# FPGA.net
KiCad netlist of a schematic drawn in Altium Designer
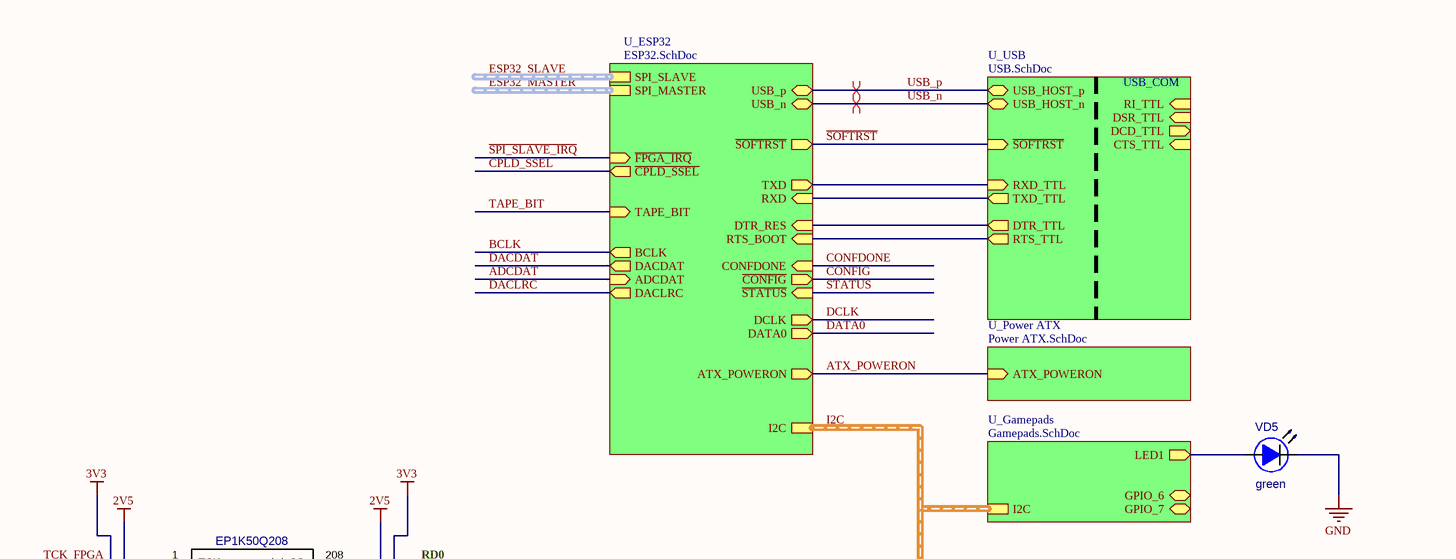
[diagram p0: FPGA.SchDoc, top]
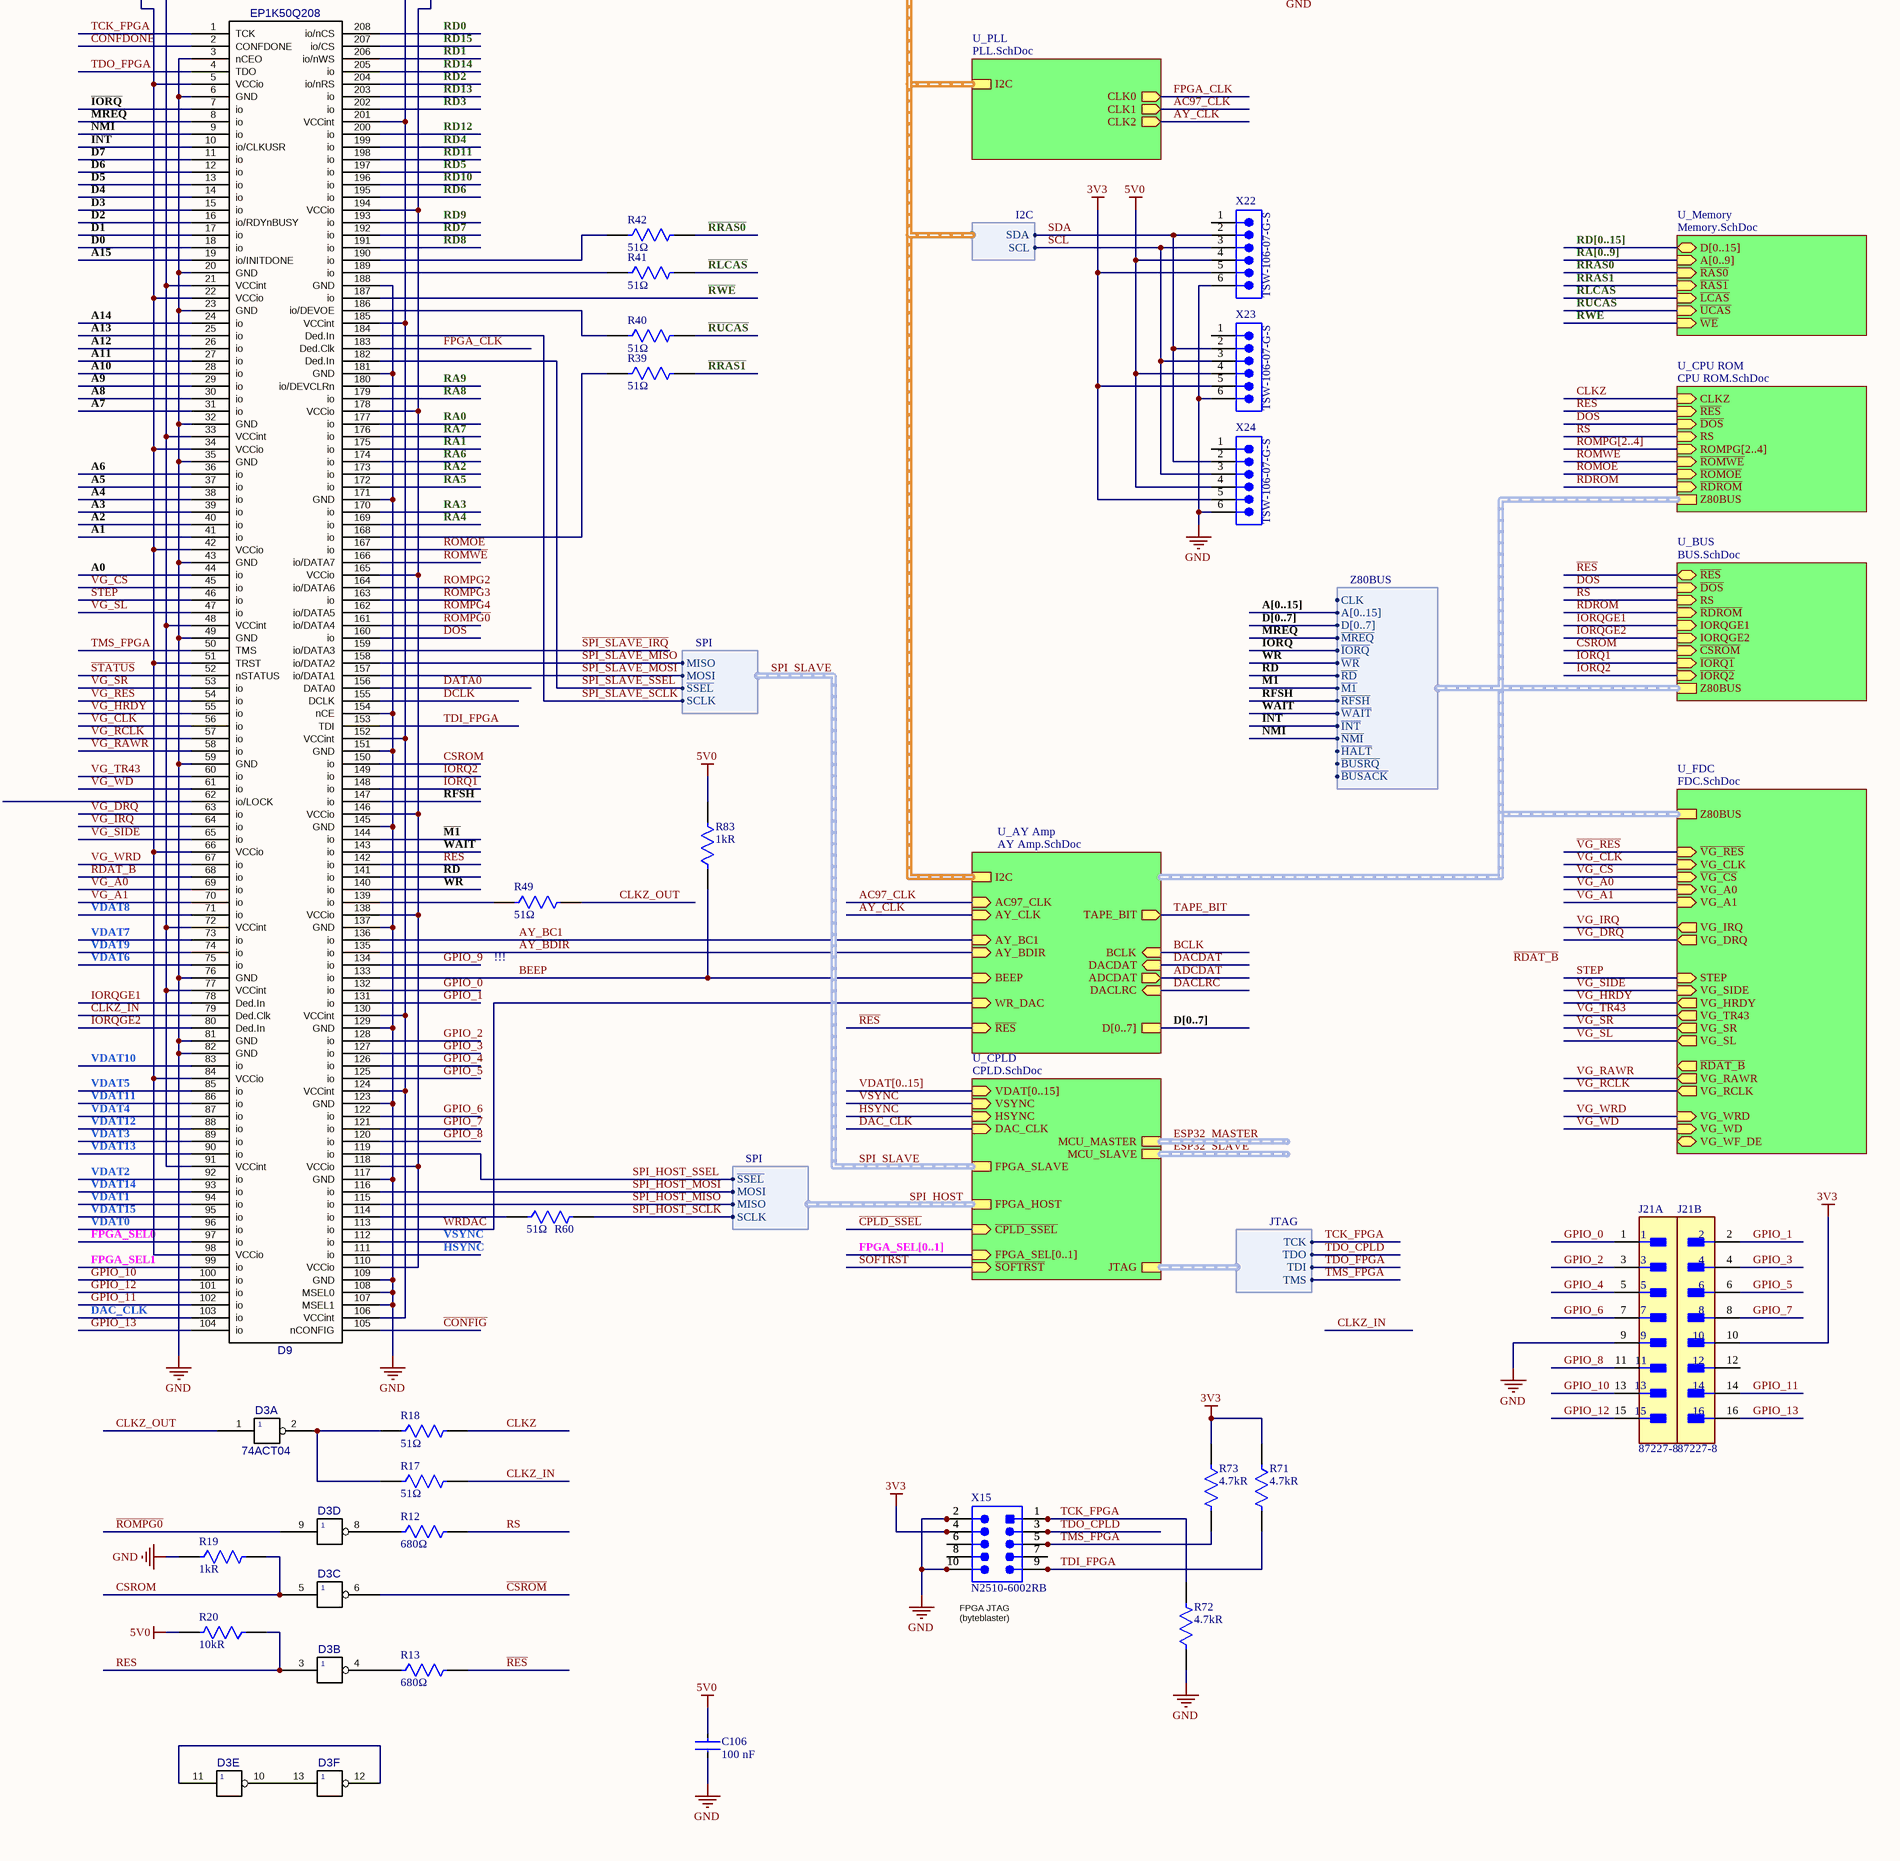
[diagram p1: FPGA.SchDoc, bottom]

(export (version "E")
  (design (tool "Eeschema 10.0.6"))
  (components
    (comp (ref "C106")
      (value "CC0805KRX7R9BB104")
      (footprint "FP-CC0805-0_85-IPC_A")
      (description "CAP CER 0.1UF 50V X7R 0805")
      (fields (field (name "CAPACITANCE") "100 nF") (field (name "MANUFACTURER") "Yageo"))
      (libsource (lib "SchLib") (part "CMP-2100-03606-3"))
    )
    (comp (ref "D3")
      (value "74ACT04")
      (footprint "SO14")
      (description "04")
      (libsource (lib "SchLib") (part "04"))
    )
    (comp (ref "D9")
      (value "EP1K50Q208")
      (footprint "PQFP208X5")
      (libsource (lib "SchLib") (part "EP1K50Q208"))
    )
    (comp (ref "J21")
      (value "87227-8")
      (footprint "FP-87227-8-MFG")
      (description "CONN HEADER VERT 16POS 2.54MM")
      (fields (field (name "MANUFACTURER") "TE Connectivity"))
      (libsource (lib "") (part "CMP-03369-000064-1_1"))
    )
    (comp (ref "R12")
      (value "680Ω")
      (footprint "FP-RT0805-IPC_A")
      (description "RES SMD 680 OHM 1% 1/8W 0805")
      (fields
        (field (name "MANUFACTURER") "Yageo")
        (field (name "MANUFACTURER PART NUMBER") "RT0805FRE07680RL")
      )
      (libsource (lib "SchLib") (part "CMP-03412-000082-1"))
    )
    (comp (ref "R13")
      (value "680Ω")
      (footprint "FP-RT0805-IPC_A")
      (description "RES SMD 680 OHM 1% 1/8W 0805")
      (fields
        (field (name "MANUFACTURER") "Yageo")
        (field (name "MANUFACTURER PART NUMBER") "RT0805FRE07680RL")
      )
      (libsource (lib "SchLib") (part "CMP-03412-000082-1"))
    )
    (comp (ref "R17")
      (value "RR1220Q-510-D")
      (footprint "FP-RR1220-IPC_A")
      (description "51Ω ±0.5% 0.1W 1/10W Chip Resistor 0805 (2012 Metric) Thin Film")
      (fields (field (name "RESISTANCE") "51Ω") (field (name "MANUFACTURER") "Susumu"))
      (libsource (lib "SchLib") (part "CMP-2001-03561-2"))
    )
    (comp (ref "R18")
      (value "RR1220Q-510-D")
      (footprint "FP-RR1220-IPC_A")
      (description "51Ω ±0.5% 0.1W 1/10W Chip Resistor 0805 (2012 Metric) Thin Film")
      (fields (field (name "RESISTANCE") "51Ω") (field (name "MANUFACTURER") "Susumu"))
      (libsource (lib "SchLib") (part "CMP-2001-03561-2"))
    )
    (comp (ref "R19")
      (value "CRCW08051K00FKEAHP")
      (footprint "FP-CRCW0805-HPe3-IPC_A")
      (description "RES Thick Film, 1kΩ, 1%, 0.5W, 100ppm/°C, 0805")
      (fields (field (name "RESISTANCE") "1kR") (field (name "MANUFACTURER") "Vishay Dale"))
      (libsource (lib "SchLib") (part "CMP-02407-004529-1"))
    )
    (comp (ref "R20")
      (value "CR0805-JW-103ELF")
      (footprint "FP-CR0805-IPC_A")
      (description "Thick Film Chip Resistors 0805 10kΩ 0.125W 5% 200ppm/°C")
      (fields (field (name "RESISTANCE") "10kR") (field (name "MANUFACTURER") "Bourns"))
      (libsource (lib "SchLib") (part "CMP-07231-003873-1"))
    )
    (comp (ref "R39")
      (value "RR1220Q-510-D")
      (footprint "FP-RR1220-IPC_A")
      (description "51Ω ±0.5% 0.1W 1/10W Chip Resistor 0805 (2012 Metric) Thin Film")
      (fields (field (name "RESISTANCE") "51Ω") (field (name "MANUFACTURER") "Susumu"))
      (libsource (lib "SchLib") (part "CMP-2001-03561-2"))
    )
    (comp (ref "R40")
      (value "RR1220Q-510-D")
      (footprint "FP-RR1220-IPC_A")
      (description "51Ω ±0.5% 0.1W 1/10W Chip Resistor 0805 (2012 Metric) Thin Film")
      (fields (field (name "RESISTANCE") "51Ω") (field (name "MANUFACTURER") "Susumu"))
      (libsource (lib "SchLib") (part "CMP-2001-03561-2"))
    )
    (comp (ref "R41")
      (value "RR1220Q-510-D")
      (footprint "FP-RR1220-IPC_A")
      (description "51Ω ±0.5% 0.1W 1/10W Chip Resistor 0805 (2012 Metric) Thin Film")
      (fields (field (name "RESISTANCE") "51Ω") (field (name "MANUFACTURER") "Susumu"))
      (libsource (lib "SchLib") (part "CMP-2001-03561-2"))
    )
    (comp (ref "R42")
      (value "RR1220Q-510-D")
      (footprint "FP-RR1220-IPC_A")
      (description "51Ω ±0.5% 0.1W 1/10W Chip Resistor 0805 (2012 Metric) Thin Film")
      (fields (field (name "RESISTANCE") "51Ω") (field (name "MANUFACTURER") "Susumu"))
      (libsource (lib "SchLib") (part "CMP-2001-03561-2"))
    )
    (comp (ref "R49")
      (value "RR1220Q-510-D")
      (footprint "FP-RR1220-IPC_A")
      (description "51Ω ±0.5% 0.1W 1/10W Chip Resistor 0805 (2012 Metric) Thin Film")
      (fields (field (name "RESISTANCE") "51Ω") (field (name "MANUFACTURER") "Susumu"))
      (libsource (lib "SchLib") (part "CMP-2001-03561-2"))
    )
    (comp (ref "R60")
      (value "RR1220Q-510-D")
      (footprint "FP-RR1220-IPC_A")
      (description "51Ω ±0.5% 0.1W 1/10W Chip Resistor 0805 (2012 Metric) Thin Film")
      (fields (field (name "RESISTANCE") "51Ω") (field (name "MANUFACTURER") "Susumu"))
      (libsource (lib "SchLib") (part "CMP-2001-03561-2"))
    )
    (comp (ref "R71")
      (value "CR0805-JW-472ELF")
      (footprint "FP-CR0805-IPC_A")
      (description "Thick Film Chip Resistors 0805 4.7kΩ 0.125W 5% 200ppm/°C")
      (fields (field (name "RESISTANCE") "4.7kR") (field (name "MANUFACTURER") "Bourns"))
      (libsource (lib "SchLib") (part "CMP-07231-004713-1"))
    )
    (comp (ref "R72")
      (value "CR0805-JW-472ELF")
      (footprint "FP-CR0805-IPC_A")
      (description "Thick Film Chip Resistors 0805 4.7kΩ 0.125W 5% 200ppm/°C")
      (fields (field (name "RESISTANCE") "4.7kR") (field (name "MANUFACTURER") "Bourns"))
      (libsource (lib "SchLib") (part "CMP-07231-004713-1"))
    )
    (comp (ref "R73")
      (value "CR0805-JW-472ELF")
      (footprint "FP-CR0805-IPC_A")
      (description "Thick Film Chip Resistors 0805 4.7kΩ 0.125W 5% 200ppm/°C")
      (fields (field (name "RESISTANCE") "4.7kR") (field (name "MANUFACTURER") "Bourns"))
      (libsource (lib "SchLib") (part "CMP-07231-004713-1"))
    )
    (comp (ref "R83")
      (value "CRCW08051K00FKEAHP")
      (footprint "FP-CRCW0805-HPe3-IPC_A")
      (description "RES Thick Film, 1kΩ, 1%, 0.5W, 100ppm/°C, 0805")
      (fields (field (name "RESISTANCE") "1kR") (field (name "MANUFACTURER") "Vishay Dale"))
      (libsource (lib "SchLib") (part "CMP-02407-004529-1"))
    )
    (comp (ref "VD5")
      (value "green")
      (footprint "LED100_LED(Primary)")
      (description "Light Emitting Diode")
      (fields (field (name "Comment") "LED"))
      (libsource (lib "SchLib") (part "LED"))
    )
    (comp (ref "X15")
      (value "N2510-6002RB")
      (footprint "3M-N2510-6002-10_V")
      (fields (field (name "PARTNUMBER") "N2510") (field (name "MANUFACTURER") "3M"))
      (libsource (lib "SchLib") (part "CMP-2000-06794-1"))
    )
    (comp (ref "X22")
      (value "TSW-106-07-G-S")
      (footprint "SMTC-TSW-106-07-X-S")
      (description "0.025\" SQ Post Header, Through-hole, Vertical, -55 to 125 degC, 2.54 mm Pitch, 6-Pin, Male, RoHS")
      (fields (field (name "MANUFACTURER") "Samtec"))
      (libsource (lib "SchLib") (part "CMP-1024-00383-1"))
    )
    (comp (ref "X23")
      (value "TSW-106-07-G-S")
      (footprint "SMTC-TSW-106-07-X-S")
      (description "0.025\" SQ Post Header, Through-hole, Vertical, -55 to 125 degC, 2.54 mm Pitch, 6-Pin, Male, RoHS")
      (fields (field (name "MANUFACTURER") "Samtec"))
      (libsource (lib "SchLib") (part "CMP-1024-00383-1"))
    )
    (comp (ref "X24")
      (value "TSW-106-07-G-S")
      (footprint "SMTC-TSW-106-07-X-S")
      (description "0.025\" SQ Post Header, Through-hole, Vertical, -55 to 125 degC, 2.54 mm Pitch, 6-Pin, Male, RoHS")
      (fields (field (name "MANUFACTURER") "Samtec"))
      (libsource (lib "SchLib") (part "CMP-1024-00383-1"))
    )
  )
  (nets
    (net (code "7") (name "+5v") (class "Default")
      (node (ref "D3") (pin "14") (pinfunction "+5v_14") (pintype "power_in"))
    )
    (net (code "8") (name "/A0") (class "Default")
      (node (ref "D9") (pin "44") (pinfunction "io_44") (pintype "passive"))
    )
    (net (code "9") (name "/A1") (class "Default")
      (node (ref "D9") (pin "41") (pinfunction "io_41") (pintype "passive"))
    )
    (net (code "10") (name "/A2") (class "Default")
      (node (ref "D9") (pin "40") (pinfunction "io_40") (pintype "passive"))
    )
    (net (code "11") (name "/A3") (class "Default")
      (node (ref "D9") (pin "39") (pinfunction "io_39") (pintype "passive"))
    )
    (net (code "12") (name "/A4") (class "Default")
      (node (ref "D9") (pin "38") (pinfunction "io_38") (pintype "passive"))
    )
    (net (code "13") (name "/A5") (class "Default")
      (node (ref "D9") (pin "37") (pinfunction "io_37") (pintype "passive"))
    )
    (net (code "14") (name "/A6") (class "Default")
      (node (ref "D9") (pin "36") (pinfunction "io_36") (pintype "passive"))
    )
    (net (code "15") (name "/A7") (class "Default")
      (node (ref "D9") (pin "31") (pinfunction "io_31") (pintype "passive"))
    )
    (net (code "16") (name "/A8") (class "Default")
      (node (ref "D9") (pin "30") (pinfunction "io_30") (pintype "passive"))
    )
    (net (code "17") (name "/A9") (class "Default")
      (node (ref "D9") (pin "29") (pinfunction "io_29") (pintype "passive"))
    )
    (net (code "18") (name "/A10") (class "Default")
      (node (ref "D9") (pin "28") (pinfunction "io_28") (pintype "passive"))
    )
    (net (code "19") (name "/A11") (class "Default")
      (node (ref "D9") (pin "27") (pinfunction "io_27") (pintype "passive"))
    )
    (net (code "20") (name "/A12") (class "Default")
      (node (ref "D9") (pin "26") (pinfunction "io_26") (pintype "passive"))
    )
    (net (code "21") (name "/A13") (class "Default")
      (node (ref "D9") (pin "25") (pinfunction "io_25") (pintype "passive"))
    )
    (net (code "22") (name "/A14") (class "Default")
      (node (ref "D9") (pin "24") (pinfunction "io_24") (pintype "passive"))
    )
    (net (code "23") (name "/A15") (class "Default")
      (node (ref "D9") (pin "19") (pinfunction "io/INITDONE_19") (pintype "passive"))
    )
    (net (code "27") (name "/AY_BC1") (class "Default")
      (node (ref "D9") (pin "136") (pinfunction "io_136") (pintype "passive"))
    )
    (net (code "28") (name "/AY_BDIR") (class "Default")
      (node (ref "D9") (pin "135") (pinfunction "io_135") (pintype "passive"))
    )
    (net (code "32") (name "/BEEP") (class "Default")
      (node (ref "D9") (pin "133") (pinfunction "io_133") (pintype "passive"))
      (node (ref "R83") (pin "1") (pinfunction "1_1") (pintype "passive"))
    )
    (net (code "33") (name "/CLKZ") (class "Default")
      (node (ref "R18") (pin "2") (pinfunction "2_2") (pintype "passive"))
    )
    (net (code "34") (name "/CLKZ_IN") (class "Default")
      (node (ref "D9") (pin "79") (pinfunction "Ded.Clk_79") (pintype "passive"))
      (node (ref "R17") (pin "2") (pinfunction "2_2") (pintype "passive"))
    )
    (net (code "35") (name "/CLKZ_OUT") (class "Default")
      (node (ref "D3") (pin "1") (pintype "passive"))
      (node (ref "R49") (pin "2") (pinfunction "2_2") (pintype "passive"))
    )
    (net (code "36") (name "/CONFDONE") (class "Default")
      (node (ref "D9") (pin "2") (pinfunction "CONFDONE_2") (pintype "passive"))
    )
    (net (code "37") (name "/CSROM") (class "Default")
      (node (ref "D3") (pin "5") (pintype "passive"))
      (node (ref "D9") (pin "150") (pinfunction "io_150") (pintype "passive"))
      (node (ref "R19") (pin "2") (pinfunction "2_2") (pintype "passive"))
    )
    (net (code "39") (name "/D0") (class "Default")
      (node (ref "D9") (pin "18") (pinfunction "io_18") (pintype "passive"))
    )
    (net (code "40") (name "/D1") (class "Default")
      (node (ref "D9") (pin "17") (pinfunction "io_17") (pintype "passive"))
    )
    (net (code "41") (name "/D2") (class "Default")
      (node (ref "D9") (pin "16") (pinfunction "io/RDYnBUSY_16") (pintype "passive"))
    )
    (net (code "42") (name "/D3") (class "Default")
      (node (ref "D9") (pin "15") (pinfunction "io_15") (pintype "passive"))
    )
    (net (code "43") (name "/D4") (class "Default")
      (node (ref "D9") (pin "14") (pinfunction "io_14") (pintype "passive"))
    )
    (net (code "44") (name "/D5") (class "Default")
      (node (ref "D9") (pin "13") (pinfunction "io_13") (pintype "passive"))
    )
    (net (code "45") (name "/D6") (class "Default")
      (node (ref "D9") (pin "12") (pinfunction "io_12") (pintype "passive"))
    )
    (net (code "46") (name "/D7") (class "Default")
      (node (ref "D9") (pin "11") (pinfunction "io_11") (pintype "passive"))
    )
    (net (code "49") (name "/DAC_CLK") (class "Default")
      (node (ref "D9") (pin "103") (pinfunction "io_103") (pintype "passive"))
    )
    (net (code "50") (name "/DATA0") (class "Default")
      (node (ref "D9") (pin "156") (pinfunction "DATA0_156") (pintype "passive"))
    )
    (net (code "52") (name "/DCLK") (class "Default")
      (node (ref "D9") (pin "155") (pinfunction "DCLK_155") (pintype "passive"))
    )
    (net (code "56") (name "/FPGA_CLK") (class "Default")
      (node (ref "D9") (pin "183") (pinfunction "Ded.Clk_183") (pintype "passive"))
    )
    (net (code "57") (name "/FPGA_SEL0") (class "Default")
      (node (ref "D9") (pin "97") (pinfunction "io_97") (pintype "passive"))
    )
    (net (code "58") (name "/FPGA_SEL1") (class "Default")
      (node (ref "D9") (pin "99") (pinfunction "io_99") (pintype "passive"))
    )
    (net (code "60") (name "/GPIO_0") (class "Default")
      (node (ref "D9") (pin "132") (pinfunction "io_132") (pintype "passive"))
      (node (ref "J21") (pin "1") (pinfunction "1_1") (pintype "passive"))
    )
    (net (code "61") (name "/GPIO_1") (class "Default")
      (node (ref "D9") (pin "131") (pinfunction "io_131") (pintype "passive"))
      (node (ref "J21") (pin "2") (pinfunction "2_2") (pintype "passive"))
    )
    (net (code "62") (name "/GPIO_2") (class "Default")
      (node (ref "D9") (pin "128") (pinfunction "io_128") (pintype "passive"))
      (node (ref "J21") (pin "3") (pinfunction "3_3") (pintype "passive"))
    )
    (net (code "63") (name "/GPIO_3") (class "Default")
      (node (ref "D9") (pin "127") (pinfunction "io_127") (pintype "passive"))
      (node (ref "J21") (pin "4") (pinfunction "4_4") (pintype "passive"))
    )
    (net (code "64") (name "/GPIO_4") (class "Default")
      (node (ref "D9") (pin "126") (pinfunction "io_126") (pintype "passive"))
      (node (ref "J21") (pin "5") (pinfunction "5_5") (pintype "passive"))
    )
    (net (code "65") (name "/GPIO_5") (class "Default")
      (node (ref "D9") (pin "125") (pinfunction "io_125") (pintype "passive"))
      (node (ref "J21") (pin "6") (pinfunction "6_6") (pintype "passive"))
    )
    (net (code "66") (name "/GPIO_6") (class "Default")
      (node (ref "D9") (pin "122") (pinfunction "io_122") (pintype "passive"))
      (node (ref "J21") (pin "7") (pinfunction "7_7") (pintype "passive"))
    )
    (net (code "68") (name "/GPIO_7") (class "Default")
      (node (ref "D9") (pin "121") (pinfunction "io_121") (pintype "passive"))
      (node (ref "J21") (pin "8") (pinfunction "8_8") (pintype "passive"))
    )
    (net (code "70") (name "/GPIO_8") (class "Default")
      (node (ref "D9") (pin "120") (pinfunction "io_120") (pintype "passive"))
      (node (ref "J21") (pin "11") (pinfunction "11_11") (pintype "passive"))
    )
    (net (code "71") (name "/GPIO_9") (class "Default")
      (node (ref "D9") (pin "134") (pinfunction "io_134") (pintype "passive"))
    )
    (net (code "72") (name "/GPIO_10") (class "Default")
      (node (ref "D9") (pin "100") (pinfunction "io_100") (pintype "passive"))
      (node (ref "J21") (pin "13") (pinfunction "13_13") (pintype "passive"))
    )
    (net (code "73") (name "/GPIO_11") (class "Default")
      (node (ref "D9") (pin "102") (pinfunction "io_102") (pintype "passive"))
      (node (ref "J21") (pin "14") (pinfunction "14_14") (pintype "passive"))
    )
    (net (code "74") (name "/GPIO_12") (class "Default")
      (node (ref "D9") (pin "101") (pinfunction "io_101") (pintype "passive"))
      (node (ref "J21") (pin "15") (pinfunction "15_15") (pintype "passive"))
    )
    (net (code "75") (name "/GPIO_13") (class "Default")
      (node (ref "D9") (pin "104") (pinfunction "io_104") (pintype "passive"))
      (node (ref "J21") (pin "16") (pinfunction "16_16") (pintype "passive"))
    )
    (net (code "76") (name "/HSYNC") (class "Default")
      (node (ref "D9") (pin "111") (pinfunction "io_111") (pintype "passive"))
    )
    (net (code "78") (name "/IORQGE1") (class "Default")
      (node (ref "D9") (pin "78") (pinfunction "Ded.In_78") (pintype "passive"))
    )
    (net (code "79") (name "/IORQGE2") (class "Default")
      (node (ref "D9") (pin "80") (pinfunction "Ded.In_80") (pintype "passive"))
    )
    (net (code "80") (name "/LED1") (class "Default")
      (node (ref "VD5") (pin "A") (pinfunction "A_A") (pintype "passive"))
    )
    (net (code "81") (name "/RA0") (class "Default")
      (node (ref "D9") (pin "177") (pinfunction "io_177") (pintype "passive"))
    )
    (net (code "82") (name "/RA1") (class "Default")
      (node (ref "D9") (pin "175") (pinfunction "io_175") (pintype "passive"))
    )
    (net (code "83") (name "/RA2") (class "Default")
      (node (ref "D9") (pin "173") (pinfunction "io_173") (pintype "passive"))
    )
    (net (code "84") (name "/RA3") (class "Default")
      (node (ref "D9") (pin "170") (pinfunction "io_170") (pintype "passive"))
    )
    (net (code "85") (name "/RA4") (class "Default")
      (node (ref "D9") (pin "169") (pinfunction "io_169") (pintype "passive"))
    )
    (net (code "86") (name "/RA5") (class "Default")
      (node (ref "D9") (pin "172") (pinfunction "io_172") (pintype "passive"))
    )
    (net (code "87") (name "/RA6") (class "Default")
      (node (ref "D9") (pin "174") (pinfunction "io_174") (pintype "passive"))
    )
    (net (code "88") (name "/RA7") (class "Default")
      (node (ref "D9") (pin "176") (pinfunction "io_176") (pintype "passive"))
    )
    (net (code "89") (name "/RA8") (class "Default")
      (node (ref "D9") (pin "179") (pinfunction "io_179") (pintype "passive"))
    )
    (net (code "90") (name "/RA9") (class "Default")
      (node (ref "D9") (pin "180") (pinfunction "io/DEVCLRn_180") (pintype "passive"))
    )
    (net (code "92") (name "/RD0") (class "Default")
      (node (ref "D9") (pin "208") (pinfunction "io/nCS_208") (pintype "passive"))
    )
    (net (code "93") (name "/RD1") (class "Default")
      (node (ref "D9") (pin "206") (pinfunction "io/nWS_206") (pintype "passive"))
    )
    (net (code "94") (name "/RD2") (class "Default")
      (node (ref "D9") (pin "204") (pinfunction "io/nRS_204") (pintype "passive"))
    )
    (net (code "95") (name "/RD3") (class "Default")
      (node (ref "D9") (pin "202") (pinfunction "io_202") (pintype "passive"))
    )
    (net (code "96") (name "/RD4") (class "Default")
      (node (ref "D9") (pin "199") (pinfunction "io_199") (pintype "passive"))
    )
    (net (code "97") (name "/RD5") (class "Default")
      (node (ref "D9") (pin "197") (pinfunction "io_197") (pintype "passive"))
    )
    (net (code "98") (name "/RD6") (class "Default")
      (node (ref "D9") (pin "195") (pinfunction "io_195") (pintype "passive"))
    )
    (net (code "99") (name "/RD7") (class "Default")
      (node (ref "D9") (pin "192") (pinfunction "io_192") (pintype "passive"))
    )
    (net (code "100") (name "/RD8") (class "Default")
      (node (ref "D9") (pin "191") (pinfunction "io_191") (pintype "passive"))
    )
    (net (code "101") (name "/RD9") (class "Default")
      (node (ref "D9") (pin "193") (pinfunction "io_193") (pintype "passive"))
    )
    (net (code "102") (name "/RD10") (class "Default")
      (node (ref "D9") (pin "196") (pinfunction "io_196") (pintype "passive"))
    )
    (net (code "103") (name "/RD11") (class "Default")
      (node (ref "D9") (pin "198") (pinfunction "io_198") (pintype "passive"))
    )
    (net (code "104") (name "/RD12") (class "Default")
      (node (ref "D9") (pin "200") (pinfunction "io_200") (pintype "passive"))
    )
    (net (code "105") (name "/RD13") (class "Default")
      (node (ref "D9") (pin "203") (pinfunction "io_203") (pintype "passive"))
    )
    (net (code "106") (name "/RD14") (class "Default")
      (node (ref "D9") (pin "205") (pinfunction "io_205") (pintype "passive"))
    )
    (net (code "107") (name "/RD15") (class "Default")
      (node (ref "D9") (pin "207") (pinfunction "io/CS_207") (pintype "passive"))
    )
    (net (code "109") (name "/RES") (class "Default")
      (node (ref "D3") (pin "3") (pintype "passive"))
      (node (ref "D9") (pin "142") (pinfunction "io_142") (pintype "passive"))
      (node (ref "R20") (pin "1") (pinfunction "1_1") (pintype "passive"))
    )
    (net (code "111") (name "/ROMPG2") (class "Default")
      (node (ref "D9") (pin "164") (pinfunction "io/DATA6_164") (pintype "passive"))
    )
    (net (code "112") (name "/ROMPG3") (class "Default")
      (node (ref "D9") (pin "163") (pinfunction "io_163") (pintype "passive"))
    )
    (net (code "113") (name "/ROMPG4") (class "Default")
      (node (ref "D9") (pin "162") (pinfunction "io/DATA5_162") (pintype "passive"))
    )
    (net (code "115") (name "/RS") (class "Default")
      (node (ref "R12") (pin "2") (pinfunction "2_2") (pintype "passive"))
    )
    (net (code "117") (name "/SCL") (class "Default")
      (node (ref "X22") (pin "3") (pinfunction "3_3") (pintype "passive"))
      (node (ref "X23") (pin "3") (pinfunction "3_3") (pintype "passive"))
      (node (ref "X24") (pin "3") (pinfunction "3_3") (pintype "passive"))
    )
    (net (code "118") (name "/SDA") (class "Default")
      (node (ref "X22") (pin "2") (pinfunction "2_2") (pintype "passive"))
      (node (ref "X23") (pin "2") (pinfunction "2_2") (pintype "passive"))
      (node (ref "X24") (pin "2") (pinfunction "2_2") (pintype "passive"))
    )
    (net (code "119") (name "/SPI_HOST_MISO") (class "Default")
      (node (ref "D9") (pin "115") (pinfunction "io_115") (pintype "passive"))
    )
    (net (code "120") (name "/SPI_HOST_MOSI") (class "Default")
      (node (ref "D9") (pin "116") (pinfunction "io_116") (pintype "passive"))
    )
    (net (code "121") (name "/SPI_HOST_SCLK") (class "Default")
      (node (ref "R60") (pin "2") (pinfunction "2_2") (pintype "passive"))
    )
    (net (code "122") (name "/SPI_HOST_SSEL") (class "Default")
      (node (ref "D9") (pin "119") (pinfunction "io_119") (pintype "passive"))
    )
    (net (code "124") (name "/SPI_SLAVE_MISO") (class "Default")
      (node (ref "D9") (pin "158") (pinfunction "io/DATA2_158") (pintype "passive"))
    )
    (net (code "125") (name "/SPI_SLAVE_MOSI") (class "Default")
      (node (ref "D9") (pin "157") (pinfunction "io/DATA1_157") (pintype "passive"))
    )
    (net (code "126") (name "/SPI_SLAVE_SCLK") (class "Default")
      (node (ref "D9") (pin "184") (pinfunction "Ded.In_184") (pintype "passive"))
    )
    (net (code "128") (name "/STEP") (class "Default")
      (node (ref "D9") (pin "46") (pinfunction "io_46") (pintype "passive"))
    )
    (net (code "130") (name "/TCK_FPGA") (class "Default")
      (node (ref "D9") (pin "1") (pinfunction "TCK_1") (pintype "passive"))
      (node (ref "R72") (pin "2") (pinfunction "2_2") (pintype "passive"))
      (node (ref "X15") (pin "1") (pinfunction "1_1") (pintype "passive"))
    )
    (net (code "131") (name "/TDI_FPGA") (class "Default")
      (node (ref "D9") (pin "153") (pinfunction "TDI_153") (pintype "passive"))
      (node (ref "R71") (pin "2") (pinfunction "2_2") (pintype "passive"))
      (node (ref "X15") (pin "9") (pinfunction "9_9") (pintype "passive"))
    )
    (net (code "132") (name "/TDO_CPLD") (class "Default")
      (node (ref "X15") (pin "3") (pinfunction "3_3") (pintype "passive"))
    )
    (net (code "133") (name "/TDO_FPGA") (class "Default")
      (node (ref "D9") (pin "4") (pinfunction "TDO_4") (pintype "passive"))
    )
    (net (code "134") (name "/TMS_FPGA") (class "Default")
      (node (ref "D9") (pin "50") (pinfunction "TMS_50") (pintype "passive"))
      (node (ref "R73") (pin "2") (pinfunction "2_2") (pintype "passive"))
      (node (ref "X15") (pin "5") (pinfunction "5_5") (pintype "passive"))
    )
    (net (code "139") (name "/VDAT0") (class "Default")
      (node (ref "D9") (pin "96") (pinfunction "io_96") (pintype "passive"))
    )
    (net (code "140") (name "/VDAT1") (class "Default")
      (node (ref "D9") (pin "94") (pinfunction "io_94") (pintype "passive"))
    )
    (net (code "141") (name "/VDAT2") (class "Default")
      (node (ref "D9") (pin "92") (pinfunction "io_92") (pintype "passive"))
    )
    (net (code "142") (name "/VDAT3") (class "Default")
      (node (ref "D9") (pin "89") (pinfunction "io_89") (pintype "passive"))
    )
    (net (code "143") (name "/VDAT4") (class "Default")
      (node (ref "D9") (pin "87") (pinfunction "io_87") (pintype "passive"))
    )
    (net (code "144") (name "/VDAT5") (class "Default")
      (node (ref "D9") (pin "85") (pinfunction "io_85") (pintype "passive"))
    )
    (net (code "145") (name "/VDAT6") (class "Default")
      (node (ref "D9") (pin "75") (pinfunction "io_75") (pintype "passive"))
    )
    (net (code "146") (name "/VDAT7") (class "Default")
      (node (ref "D9") (pin "73") (pinfunction "io_73") (pintype "passive"))
    )
    (net (code "147") (name "/VDAT8") (class "Default")
      (node (ref "D9") (pin "71") (pinfunction "io_71") (pintype "passive"))
    )
    (net (code "148") (name "/VDAT9") (class "Default")
      (node (ref "D9") (pin "74") (pinfunction "io_74") (pintype "passive"))
    )
    (net (code "149") (name "/VDAT10") (class "Default")
      (node (ref "D9") (pin "83") (pinfunction "io_83") (pintype "passive"))
    )
    (net (code "150") (name "/VDAT11") (class "Default")
      (node (ref "D9") (pin "86") (pinfunction "io_86") (pintype "passive"))
    )
    (net (code "151") (name "/VDAT12") (class "Default")
      (node (ref "D9") (pin "88") (pinfunction "io_88") (pintype "passive"))
    )
    (net (code "152") (name "/VDAT13") (class "Default")
      (node (ref "D9") (pin "90") (pinfunction "io_90") (pintype "passive"))
    )
    (net (code "153") (name "/VDAT14") (class "Default")
      (node (ref "D9") (pin "93") (pinfunction "io_93") (pintype "passive"))
    )
    (net (code "154") (name "/VDAT15") (class "Default")
      (node (ref "D9") (pin "95") (pinfunction "io_95") (pintype "passive"))
    )
    (net (code "156") (name "/VG_A0") (class "Default")
      (node (ref "D9") (pin "69") (pinfunction "io_69") (pintype "passive"))
    )
    (net (code "157") (name "/VG_A1") (class "Default")
      (node (ref "D9") (pin "70") (pinfunction "io_70") (pintype "passive"))
    )
    (net (code "158") (name "/VG_CLK") (class "Default")
      (node (ref "D9") (pin "56") (pinfunction "io_56") (pintype "passive"))
    )
    (net (code "159") (name "/VG_DRQ") (class "Default")
      (node (ref "D9") (pin "63") (pinfunction "io_63") (pintype "passive"))
    )
    (net (code "160") (name "/VG_HRDY") (class "Default")
      (node (ref "D9") (pin "55") (pinfunction "io_55") (pintype "passive"))
    )
    (net (code "161") (name "/VG_IRQ") (class "Default")
      (node (ref "D9") (pin "64") (pinfunction "io_64") (pintype "passive"))
    )
    (net (code "162") (name "/VG_RAWR") (class "Default")
      (node (ref "D9") (pin "58") (pinfunction "io_58") (pintype "passive"))
    )
    (net (code "163") (name "/VG_RCLK") (class "Default")
      (node (ref "D9") (pin "57") (pinfunction "io_57") (pintype "passive"))
    )
    (net (code "164") (name "/VG_SIDE") (class "Default")
      (node (ref "D9") (pin "65") (pinfunction "io_65") (pintype "passive"))
    )
    (net (code "165") (name "/VG_SL") (class "Default")
      (node (ref "D9") (pin "47") (pinfunction "io_47") (pintype "passive"))
    )
    (net (code "166") (name "/VG_SR") (class "Default")
      (node (ref "D9") (pin "53") (pinfunction "io_53") (pintype "passive"))
    )
    (net (code "167") (name "/VG_TR43") (class "Default")
      (node (ref "D9") (pin "60") (pinfunction "io_60") (pintype "passive"))
    )
    (net (code "168") (name "/VG_WD") (class "Default")
      (node (ref "D9") (pin "61") (pinfunction "io_61") (pintype "passive"))
    )
    (net (code "170") (name "/VG_WRD") (class "Default")
      (node (ref "D9") (pin "67") (pinfunction "io_67") (pintype "passive"))
    )
    (net (code "171") (name "/VSYNC") (class "Default")
      (node (ref "D9") (pin "112") (pinfunction "io_112") (pintype "passive"))
    )
    (net (code "172") (name "/WRDAC") (class "Default")
      (node (ref "D9") (pin "113") (pinfunction "io_113") (pintype "passive"))
    )
    (net (code "178") (name "/~{CONFIG}") (class "Default")
      (node (ref "D9") (pin "105") (pinfunction "nCONFIG_105") (pintype "passive"))
    )
    (net (code "180") (name "/~{CSROM}") (class "Default") (node (ref "D3") (pin "6") (pintype "passive")))
    (net (code "181") (name "/~{DOS}") (class "Default")
      (node (ref "D9") (pin "160") (pinfunction "io_160") (pintype "passive"))
    )
    (net (code "182") (name "/~{INT}") (class "Default")
      (node (ref "D9") (pin "10") (pinfunction "io/CLKUSR_10") (pintype "passive"))
    )
    (net (code "183") (name "/~{IORQ1}") (class "Default")
      (node (ref "D9") (pin "148") (pinfunction "io_148") (pintype "passive"))
    )
    (net (code "184") (name "/~{IORQ2}") (class "Default")
      (node (ref "D9") (pin "149") (pinfunction "io_149") (pintype "passive"))
    )
    (net (code "185") (name "/~{IORQ}") (class "Default")
      (node (ref "D9") (pin "7") (pinfunction "io_7") (pintype "passive"))
    )
    (net (code "186") (name "/~{M1}") (class "Default")
      (node (ref "D9") (pin "144") (pinfunction "io_144") (pintype "passive"))
    )
    (net (code "187") (name "/~{MREQ}") (class "Default")
      (node (ref "D9") (pin "8") (pinfunction "io_8") (pintype "passive"))
    )
    (net (code "188") (name "/~{NMI}") (class "Default")
      (node (ref "D9") (pin "9") (pinfunction "io_9") (pintype "passive"))
    )
    (net (code "189") (name "/~{RDAT_B}") (class "Default")
      (node (ref "D9") (pin "68") (pinfunction "io_68") (pintype "passive"))
    )
    (net (code "192") (name "/~{RD}") (class "Default")
      (node (ref "D9") (pin "141") (pinfunction "io_141") (pintype "passive"))
    )
    (net (code "193") (name "/~{RES}") (class "Default")
      (node (ref "R13") (pin "2") (pinfunction "2_2") (pintype "passive"))
    )
    (net (code "194") (name "/~{RFSH}") (class "Default")
      (node (ref "D9") (pin "147") (pinfunction "io_147") (pintype "passive"))
    )
    (net (code "195") (name "/~{RLCAS}") (class "Default")
      (node (ref "R41") (pin "2") (pinfunction "2_2") (pintype "passive"))
    )
    (net (code "196") (name "/~{ROMOE}") (class "Default")
      (node (ref "D9") (pin "167") (pinfunction "io_167") (pintype "passive"))
    )
    (net (code "197") (name "/~{ROMPG0}") (class "Default")
      (node (ref "D3") (pin "9") (pintype "passive"))
      (node (ref "D9") (pin "161") (pinfunction "io/DATA4_161") (pintype "passive"))
    )
    (net (code "198") (name "/~{ROMWE}") (class "Default")
      (node (ref "D9") (pin "166") (pinfunction "io/DATA7_166") (pintype "passive"))
    )
    (net (code "199") (name "/~{RRAS0}") (class "Default")
      (node (ref "R42") (pin "2") (pinfunction "2_2") (pintype "passive"))
    )
    (net (code "200") (name "/~{RRAS1}") (class "Default")
      (node (ref "R39") (pin "2") (pinfunction "2_2") (pintype "passive"))
    )
    (net (code "201") (name "/~{RUCAS}") (class "Default")
      (node (ref "R40") (pin "2") (pinfunction "2_2") (pintype "passive"))
    )
    (net (code "202") (name "/~{RWE}") (class "Default")
      (node (ref "D9") (pin "187") (pinfunction "io_187") (pintype "passive"))
    )
    (net (code "204") (name "/~{SPI_SLAVE_IRQ}") (class "Default")
      (node (ref "D9") (pin "159") (pinfunction "io/DATA3_159") (pintype "passive"))
    )
    (net (code "205") (name "/~{SPI_SLAVE_SSEL}") (class "Default")
      (node (ref "D9") (pin "182") (pinfunction "Ded.In_182") (pintype "passive"))
    )
    (net (code "206") (name "/~{STATUS}") (class "Default")
      (node (ref "D9") (pin "52") (pinfunction "nSTATUS_52") (pintype "passive"))
    )
    (net (code "207") (name "/~{VG_CS}") (class "Default")
      (node (ref "D9") (pin "45") (pinfunction "io_45") (pintype "passive"))
    )
    (net (code "208") (name "/~{VG_RES}") (class "Default")
      (node (ref "D9") (pin "54") (pinfunction "io_54") (pintype "passive"))
    )
    (net (code "209") (name "/~{WAIT}") (class "Default")
      (node (ref "D9") (pin "143") (pinfunction "io_143") (pintype "passive"))
    )
    (net (code "210") (name "/~{WR}") (class "Default")
      (node (ref "D9") (pin "140") (pinfunction "io_140") (pintype "passive"))
    )
    (net (code "211") (name "2V5") (class "Default")
      (node (ref "D9") (pin "106") (pinfunction "VCCint_106") (pintype "passive"))
      (node (ref "D9") (pin "124") (pinfunction "VCCint_124") (pintype "passive"))
      (node (ref "D9") (pin "130") (pinfunction "VCCint_130") (pintype "passive"))
      (node (ref "D9") (pin "152") (pinfunction "VCCint_152") (pintype "passive"))
      (node (ref "D9") (pin "185") (pinfunction "VCCint_185") (pintype "passive"))
      (node (ref "D9") (pin "201") (pinfunction "VCCint_201") (pintype "passive"))
      (node (ref "D9") (pin "21") (pinfunction "VCCint_21") (pintype "passive"))
      (node (ref "D9") (pin "33") (pinfunction "VCCint_33") (pintype "passive"))
      (node (ref "D9") (pin "48") (pinfunction "VCCint_48") (pintype "passive"))
      (node (ref "D9") (pin "72") (pinfunction "VCCint_72") (pintype "passive"))
      (node (ref "D9") (pin "77") (pinfunction "VCCint_77") (pintype "passive"))
      (node (ref "D9") (pin "91") (pinfunction "VCCint_91") (pintype "passive"))
    )
    (net (code "212") (name "3V3") (class "Default")
      (node (ref "D9") (pin "110") (pinfunction "VCCio_110") (pintype "passive"))
      (node (ref "D9") (pin "118") (pinfunction "VCCio_118") (pintype "passive"))
      (node (ref "D9") (pin "138") (pinfunction "VCCio_138") (pintype "passive"))
      (node (ref "D9") (pin "146") (pinfunction "VCCio_146") (pintype "passive"))
      (node (ref "D9") (pin "165") (pinfunction "VCCio_165") (pintype "passive"))
      (node (ref "D9") (pin "178") (pinfunction "VCCio_178") (pintype "passive"))
      (node (ref "D9") (pin "194") (pinfunction "VCCio_194") (pintype "passive"))
      (node (ref "D9") (pin "22") (pinfunction "VCCio_22") (pintype "passive"))
      (node (ref "D9") (pin "34") (pinfunction "VCCio_34") (pintype "passive"))
      (node (ref "D9") (pin "42") (pinfunction "VCCio_42") (pintype "passive"))
      (node (ref "D9") (pin "5") (pinfunction "VCCio_5") (pintype "passive"))
      (node (ref "D9") (pin "51") (pinfunction "TRST_51") (pintype "passive"))
      (node (ref "D9") (pin "66") (pinfunction "VCCio_66") (pintype "passive"))
      (node (ref "D9") (pin "84") (pinfunction "VCCio_84") (pintype "passive"))
      (node (ref "D9") (pin "98") (pinfunction "VCCio_98") (pintype "passive"))
      (node (ref "J21") (pin "10") (pinfunction "10_10") (pintype "passive"))
      (node (ref "R71") (pin "1") (pinfunction "1_1") (pintype "passive"))
      (node (ref "R73") (pin "1") (pinfunction "1_1") (pintype "passive"))
      (node (ref "X15") (pin "4") (pinfunction "4_4") (pintype "passive"))
      (node (ref "X22") (pin "5") (pinfunction "5_5") (pintype "passive"))
      (node (ref "X23") (pin "5") (pinfunction "5_5") (pintype "passive"))
      (node (ref "X24") (pin "5") (pinfunction "5_5") (pintype "passive"))
    )
    (net (code "213") (name "5V0") (class "Default")
      (node (ref "C106") (pin "1") (pinfunction "1_1") (pintype "passive"))
      (node (ref "R20") (pin "2") (pinfunction "2_2") (pintype "passive"))
      (node (ref "R83") (pin "2") (pinfunction "2_2") (pintype "passive"))
      (node (ref "X22") (pin "4") (pinfunction "4_4") (pintype "passive"))
      (node (ref "X23") (pin "4") (pinfunction "4_4") (pintype "passive"))
      (node (ref "X24") (pin "4") (pinfunction "4_4") (pintype "passive"))
    )
    (net (code "214") (name "GND") (class "Default")
      (node (ref "C106") (pin "2") (pinfunction "2_2") (pintype "passive"))
      (node (ref "D3") (pin "7") (pinfunction "GND_7") (pintype "power_in"))
      (node (ref "D9") (pin "107") (pinfunction "MSEL1_107") (pintype "passive"))
      (node (ref "D9") (pin "108") (pinfunction "MSEL0_108") (pintype "passive"))
      (node (ref "D9") (pin "109") (pinfunction "GND_109") (pintype "passive"))
      (node (ref "D9") (pin "117") (pinfunction "GND_117") (pintype "passive"))
      (node (ref "D9") (pin "123") (pinfunction "GND_123") (pintype "passive"))
      (node (ref "D9") (pin "129") (pinfunction "GND_129") (pintype "passive"))
      (node (ref "D9") (pin "137") (pinfunction "GND_137") (pintype "passive"))
      (node (ref "D9") (pin "145") (pinfunction "GND_145") (pintype "passive"))
      (node (ref "D9") (pin "151") (pinfunction "GND_151") (pintype "passive"))
      (node (ref "D9") (pin "154") (pinfunction "nCE_154") (pintype "passive"))
      (node (ref "D9") (pin "171") (pinfunction "GND_171") (pintype "passive"))
      (node (ref "D9") (pin "181") (pinfunction "GND_181") (pintype "passive"))
      (node (ref "D9") (pin "188") (pinfunction "GND_188") (pintype "passive"))
      (node (ref "D9") (pin "20") (pinfunction "GND_20") (pintype "passive"))
      (node (ref "D9") (pin "23") (pinfunction "GND_23") (pintype "passive"))
      (node (ref "D9") (pin "3") (pinfunction "nCEO_3") (pintype "passive"))
      (node (ref "D9") (pin "32") (pinfunction "GND_32") (pintype "passive"))
      (node (ref "D9") (pin "35") (pinfunction "GND_35") (pintype "passive"))
      (node (ref "D9") (pin "43") (pinfunction "GND_43") (pintype "passive"))
      (node (ref "D9") (pin "49") (pinfunction "GND_49") (pintype "passive"))
      (node (ref "D9") (pin "59") (pinfunction "GND_59") (pintype "passive"))
      (node (ref "D9") (pin "6") (pinfunction "GND_6") (pintype "passive"))
      (node (ref "D9") (pin "76") (pinfunction "GND_76") (pintype "passive"))
      (node (ref "D9") (pin "81") (pinfunction "GND_81") (pintype "passive"))
      (node (ref "D9") (pin "82") (pinfunction "GND_82") (pintype "passive"))
      (node (ref "J21") (pin "9") (pinfunction "9_9") (pintype "passive"))
      (node (ref "R19") (pin "1") (pinfunction "1_1") (pintype "passive"))
      (node (ref "R72") (pin "1") (pinfunction "1_1") (pintype "passive"))
      (node (ref "VD5") (pin "K") (pinfunction "K_K") (pintype "passive"))
      (node (ref "X15") (pin "10") (pinfunction "10_10") (pintype "passive"))
      (node (ref "X15") (pin "2") (pinfunction "2_2") (pintype "passive"))
      (node (ref "X22") (pin "6") (pinfunction "6_6") (pintype "passive"))
      (node (ref "X23") (pin "6") (pinfunction "6_6") (pintype "passive"))
      (node (ref "X24") (pin "6") (pinfunction "6_6") (pintype "passive"))
    )
    (net (code "215") (name "Net-(D3-Pad2)") (class "Default")
      (node (ref "D3") (pin "2") (pintype "passive"))
      (node (ref "R17") (pin "1") (pinfunction "1_1") (pintype "passive"))
      (node (ref "R18") (pin "1") (pinfunction "1_1") (pintype "passive"))
    )
    (net (code "216") (name "Net-(D3-Pad4)") (class "Default")
      (node (ref "D3") (pin "4") (pintype "passive"))
      (node (ref "R13") (pin "1") (pinfunction "1_1") (pintype "passive"))
    )
    (net (code "217") (name "Net-(D3-Pad8)") (class "Default")
      (node (ref "D3") (pin "8") (pintype "passive"))
      (node (ref "R12") (pin "1") (pinfunction "1_1") (pintype "passive"))
    )
    (net (code "218") (name "Net-(D3-Pad10)") (class "Default")
      (node (ref "D3") (pin "10") (pintype "passive"))
      (node (ref "D3") (pin "13") (pintype "passive"))
    )
    (net (code "219") (name "Net-(D3-Pad11)") (class "Default")
      (node (ref "D3") (pin "11") (pintype "passive"))
      (node (ref "D3") (pin "12") (pintype "passive"))
    )
    (net (code "220") (name "Net-(D9-io-Pad114)") (class "Default")
      (node (ref "D9") (pin "114") (pinfunction "io_114") (pintype "passive"))
      (node (ref "R60") (pin "1") (pinfunction "1_1") (pintype "passive"))
    )
    (net (code "221") (name "Net-(D9-io-Pad139)") (class "Default")
      (node (ref "D9") (pin "139") (pinfunction "io_139") (pintype "passive"))
      (node (ref "R49") (pin "1") (pinfunction "1_1") (pintype "passive"))
    )
    (net (code "222") (name "Net-(D9-io-Pad168)") (class "Default")
      (node (ref "D9") (pin "168") (pinfunction "io_168") (pintype "passive"))
      (node (ref "R39") (pin "1") (pinfunction "1_1") (pintype "passive"))
    )
    (net (code "223") (name "Net-(D9-io-Pad189)") (class "Default")
      (node (ref "D9") (pin "189") (pinfunction "io_189") (pintype "passive"))
      (node (ref "R41") (pin "1") (pinfunction "1_1") (pintype "passive"))
    )
    (net (code "224") (name "Net-(D9-io-Pad190)") (class "Default")
      (node (ref "D9") (pin "190") (pinfunction "io_190") (pintype "passive"))
      (node (ref "R42") (pin "1") (pinfunction "1_1") (pintype "passive"))
    )
    (net (code "225") (name "Net-(D9-io{slash}DEVOE)") (class "Default")
      (node (ref "D9") (pin "186") (pinfunction "io/DEVOE_186") (pintype "passive"))
      (node (ref "R40") (pin "1") (pinfunction "1_1") (pintype "passive"))
    )
    (net (code "226") (name "Net-(X15-Pad6)") (class "Default")
      (node (ref "X15") (pin "6") (pinfunction "6_6") (pintype "passive"))
    )
    (net (code "227") (name "Net-(X15-Pad7)") (class "Default")
      (node (ref "X15") (pin "7") (pinfunction "7_7") (pintype "passive"))
    )
    (net (code "228") (name "Net-(X15-Pad8)") (class "Default")
      (node (ref "X15") (pin "8") (pinfunction "8_8") (pintype "passive"))
    )
    (net (code "229") (name "unconnected-(D9-io{slash}LOCK-Pad62)") (class "Default")
      (node (ref "D9") (pin "62") (pinfunction "io/LOCK_62") (pintype "passive"))
    )
    (net (code "230") (name "unconnected-(J21-Pad12)") (class "Default")
      (node (ref "J21") (pin "12") (pinfunction "12_12") (pintype "passive"))
    )
    (net (code "231") (name "unconnected-(X22-Pad1)") (class "Default")
      (node (ref "X22") (pin "1") (pinfunction "1_1") (pintype "passive"))
    )
    (net (code "232") (name "unconnected-(X23-Pad1)") (class "Default")
      (node (ref "X23") (pin "1") (pinfunction "1_1") (pintype "passive"))
    )
    (net (code "233") (name "unconnected-(X24-Pad1)") (class "Default")
      (node (ref "X24") (pin "1") (pinfunction "1_1") (pintype "passive"))
    )
  )
)
